# CPUBoard_p3.net
KiCad netlist of a schematic drawn in Altium Designer
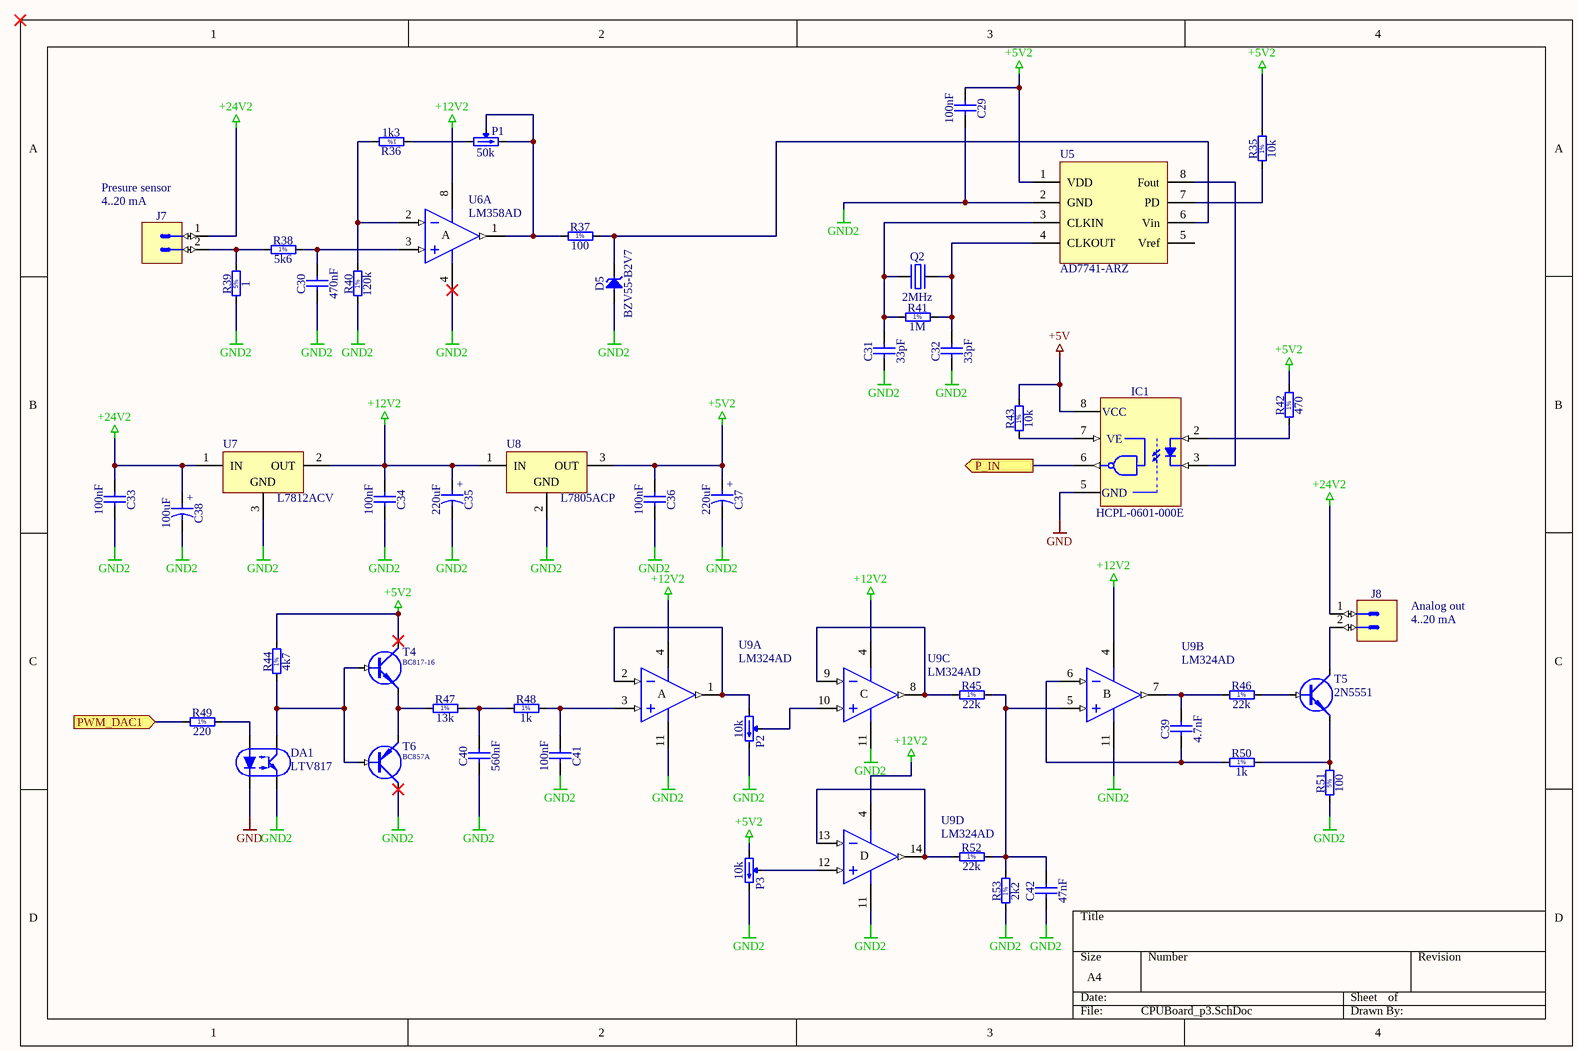
[diagram p0: CPUBoard_p3.SchDoc]

(export (version "E")
  (design (tool "Eeschema 10.0.6"))
  (components
    (comp (ref "C29")
      (value "100nF")
      (footprint "CAPC2012X135N")
      (description "Non-polarised capacitor")
      (fields
        (field (name "PART NUMBER") "CC0805_100NF_50V_10%_X7R")
        (field (name "VOLTAGE") "50V")
        (field (name "AUTHOR") "CERN DEM JLC")
      )
      (libsource (lib "Capacitors") (part "Capacitor - non polarized"))
    )
    (comp (ref "C30")
      (value "470nF")
      (footprint "CAPC2012X110N")
      (description "Non-polarised capacitor")
      (fields
        (field (name "PART NUMBER") "CC0805_470NF_50V_10%_X7R")
        (field (name "VOLTAGE") "50V")
        (field (name "AUTHOR") "CERN DEM JLC")
      )
      (libsource (lib "Capacitors") (part "Capacitor - non polarized"))
    )
    (comp (ref "C31")
      (value "33pF")
      (footprint "CAPC2012X135N")
      (description "Non-polarised capacitor")
      (fields
        (field (name "PART NUMBER") "CC0805_33PF_50V_5%_NP0")
        (field (name "VOLTAGE") "50V")
        (field (name "AUTHOR") "CERN DEM JLC")
      )
      (libsource (lib "Capacitors") (part "Capacitor - non polarized"))
    )
    (comp (ref "C32")
      (value "33pF")
      (footprint "CAPC2012X135N")
      (description "Non-polarised capacitor")
      (fields
        (field (name "PART NUMBER") "CC0805_33PF_50V_5%_NP0")
        (field (name "VOLTAGE") "50V")
        (field (name "AUTHOR") "CERN DEM JLC")
      )
      (libsource (lib "Capacitors") (part "Capacitor - non polarized"))
    )
    (comp (ref "C33")
      (value "100nF")
      (footprint "CAPC2012X135N")
      (description "Non-polarised capacitor")
      (fields
        (field (name "PART NUMBER") "CC0805_100NF_50V_10%_X7R")
        (field (name "VOLTAGE") "50V")
        (field (name "AUTHOR") "CERN DEM JLC")
      )
      (libsource (lib "Capacitors") (part "Capacitor - non polarized"))
    )
    (comp (ref "C34")
      (value "100nF")
      (footprint "CAPC2012X135N")
      (description "Non-polarised capacitor")
      (fields
        (field (name "PART NUMBER") "CC0805_100NF_50V_10%_X7R")
        (field (name "VOLTAGE") "50V")
        (field (name "AUTHOR") "CERN DEM JLC")
      )
      (libsource (lib "Capacitors") (part "Capacitor - non polarized"))
    )
    (comp (ref "C35")
      (value "220uF")
      (footprint "CAPPR350-850X1300")
      (description "Polarised capacitor")
      (fields
        (field (name "PART NUMBER") "CAER_220UF_25V_20%_RUBYCON_25YXF220M8X11.5")
        (field (name "VOLTAGE") "25V")
        (field (name "AUTHOR") "CERN DEM JLC")
      )
      (libsource (lib "Capacitors") (part "Capacitor - polarized"))
    )
    (comp (ref "C36")
      (value "100nF")
      (footprint "CAPC2012X135N")
      (description "Non-polarised capacitor")
      (fields
        (field (name "PART NUMBER") "CC0805_100NF_50V_10%_X7R")
        (field (name "VOLTAGE") "50V")
        (field (name "AUTHOR") "CERN DEM JLC")
      )
      (libsource (lib "Capacitors") (part "Capacitor - non polarized"))
    )
    (comp (ref "C37")
      (value "220uF")
      (footprint "CAPPR350-850X1300")
      (description "Polarised capacitor")
      (fields
        (field (name "PART NUMBER") "CAER_220UF_25V_20%_RUBYCON_25YXF220M8X11.5")
        (field (name "VOLTAGE") "25V")
        (field (name "AUTHOR") "CERN DEM JLC")
      )
      (libsource (lib "Capacitors") (part "Capacitor - polarized"))
    )
    (comp (ref "C38")
      (value "100uF")
      (footprint "CAPPR500-1050X1750")
      (description "Polarised capacitor")
      (fields
        (field (name "PART NUMBER") "CAER_100UF_63V_20%_500-1050X1750_LESR0R190")
        (field (name "VOLTAGE") "63V")
        (field (name "AUTHOR") "CERN DEM JLC")
      )
      (libsource (lib "Capacitors") (part "Capacitor - polarized"))
    )
    (comp (ref "C39")
      (value "4.7nF")
      (footprint "CAPC2012X135N")
      (description "Non-polarised capacitor")
      (fields
        (field (name "PART NUMBER") "CC0805_4.7NF_50V_10%_X7R")
        (field (name "VOLTAGE") "50V")
        (field (name "AUTHOR") "CERN DEM JLC")
      )
      (libsource (lib "Capacitors") (part "Capacitor - non polarized"))
    )
    (comp (ref "C40")
      (value "560nF")
      (footprint "CAPC2012X110N")
      (description "Non-polarised capacitor")
      (fields
        (field (name "PART NUMBER") "CC0805_470NF_50V_10%_X7R")
        (field (name "VOLTAGE") "50V")
        (field (name "AUTHOR") "CERN DEM JLC")
      )
      (libsource (lib "Capacitors") (part "Capacitor - non polarized"))
    )
    (comp (ref "C41")
      (value "100nF")
      (footprint "CAPC2012X135N")
      (description "Non-polarised capacitor")
      (fields
        (field (name "PART NUMBER") "CC0805_100NF_50V_10%_X7R")
        (field (name "VOLTAGE") "50V")
        (field (name "AUTHOR") "CERN DEM JLC")
      )
      (libsource (lib "Capacitors") (part "Capacitor - non polarized"))
    )
    (comp (ref "C42")
      (value "47nF")
      (footprint "CAPC2013X100N")
      (description "Non-polarised capacitor")
      (fields
        (field (name "PART NUMBER") "CC0805_47NF_50V_10%_X7R")
        (field (name "VOLTAGE") "50V")
        (field (name "AUTHOR") "CERN DEM JLC")
      )
      (libsource (lib "Capacitors") (part "Capacitor - non polarized"))
    )
    (comp (ref "D5")
      (value "BZV55-B2V7")
      (footprint "DIOMELF3515N")
      (description "Zener Diode")
      (fields
        (field (name "VOLTAGE") "2V7")
        (field (name "POWER") "500mW")
        (field (name "AUTHOR") "CERN DEM JLC")
      )
      (libsource (lib "ICs And Semiconductors") (part "Diode Zener"))
    )
    (comp (ref "DA1")
      (value "LTV817")
      (footprint "DIL4-300a")
      (libsource (lib "Opto Coupler") (part "LTV817"))
    )
    (comp (ref "IC1")
      (value "HCPL-0601-000E")
      (footprint "SOIC127P600X330-8N")
      (description "Single Optocoupler")
      (fields (field (name "MANUFACTURER") "AVAGO TECHNOLOGIES") (field (name "AUTHOR") "CERN DEM JLC"))
      (libsource (lib "ICs And Semiconductors") (part "Optocoupler Type8"))
    )
    (comp (ref "J7")
      (value "KK®")
      (footprint "MOLEX_22-27-2021")
      (description "Connector 2 Male")
      (fields
        (field (name "PART NUMBER") "MOLEX_22-27-2021")
        (field (name "MANUFACTURER") "MOLEX")
        (field (name "AUTHOR") "CERN DEM JLC")
      )
      (libsource (lib "Connectors") (part "Connector 2 Male"))
    )
    (comp (ref "J8")
      (value "KK®")
      (footprint "MOLEX_22-27-2021")
      (description "Connector 2 Male")
      (fields
        (field (name "PART NUMBER") "MOLEX_22-27-2021")
        (field (name "MANUFACTURER") "MOLEX")
        (field (name "AUTHOR") "CERN DEM JLC")
      )
      (libsource (lib "") (part "Connector 2 Male_1"))
    )
    (comp (ref "P1")
      (value "50k")
      (footprint "TRIM_BOURNS_3296Y")
      (description "Trimming Potentiometer")
      (fields
        (field (name "PART NUMBER") "TRIM_25T_50K_BOURNS_3296Y-1-503LF")
        (field (name "POWER") "0.5W")
        (field (name "AUTHOR") "CERN DEM JLC")
      )
      (libsource (lib "Resistors") (part "Trimming Potentiometer"))
    )
    (comp (ref "P2")
      (value "10k")
      (footprint "TRIM_BOURNS_3296Y")
      (description "Trimming Potentiometer")
      (fields
        (field (name "PART NUMBER") "TRIM_25T_10K_BOURNS_3296Y-1-103LF")
        (field (name "POWER") "0.5W")
        (field (name "AUTHOR") "CERN DEM JLC")
      )
      (libsource (lib "Resistors") (part "Trimming Potentiometer"))
    )
    (comp (ref "P3")
      (value "10k")
      (footprint "TRIM_BOURNS_3296Y")
      (description "Trimming Potentiometer")
      (fields
        (field (name "PART NUMBER") "TRIM_25T_10K_BOURNS_3296Y-1-103LF")
        (field (name "POWER") "0.5W")
        (field (name "AUTHOR") "CERN DEM JLC")
      )
      (libsource (lib "Resistors") (part "Trimming Potentiometer"))
    )
    (comp (ref "Q2")
      (value "2MHz")
      (footprint "XTAL_HC-49/U-S")
      (description "Quartz Crystal")
      (fields
        (field (name "PART NUMBER") "XTAL_5MHZ_CITIZEN_HC49US5.000MABJ-UB")
        (field (name "MANUFACTURER") "CITIZEN FINETECH MIYOTA CO")
        (field (name "AUTHOR") "CERN DEM JLC")
      )
      (libsource (lib "ICs And Semiconductors") (part "Quartz Crystal"))
    )
    (comp (ref "R35")
      (value "10k")
      (footprint "RESC2012X60N")
      (description "Resistor - 1%")
      (fields
        (field (name "PART NUMBER") "R0805_10K_1%_0.125W_100PPM")
        (field (name "POWER") "0.125W")
        (field (name "AUTHOR") "CERN DEM JLC")
      )
      (libsource (lib "Resistors") (part "Resistor - 1%"))
    )
    (comp (ref "R36")
      (value "1k3")
      (footprint "RESC2012X60N")
      (description "Resistor - 1%")
      (fields
        (field (name "PART NUMBER") "R0805_1K3_1%_0.125W_100PPM")
        (field (name "POWER") "0.125W")
        (field (name "AUTHOR") "CERN DEM JLC")
      )
      (libsource (lib "Resistors") (part "Resistor - 1%"))
    )
    (comp (ref "R37")
      (value "100")
      (footprint "RESC2012X60N")
      (description "Resistor - 1%")
      (fields
        (field (name "PART NUMBER") "R0805_100R_1%_0.125W_100PPM")
        (field (name "POWER") "0.125W")
        (field (name "AUTHOR") "CERN DEM JLC")
      )
      (libsource (lib "Resistors") (part "Resistor - 1%"))
    )
    (comp (ref "R38")
      (value "5k6")
      (footprint "RESC2012X60N")
      (description "Resistor - 1%")
      (fields
        (field (name "PART NUMBER") "R0805_5K6_1%_0.125W_100PPM")
        (field (name "POWER") "0.125W")
        (field (name "AUTHOR") "CERN DEM JLC")
      )
      (libsource (lib "Resistors") (part "Resistor - 1%"))
    )
    (comp (ref "R39")
      (value "1")
      (footprint "RESC3225X70N")
      (description "Resistor - 0,1%")
      (fields
        (field (name "PART NUMBER") "R1210_51R_5%_0.5W_200PPM_PANASONIC_ERJP")
        (field (name "POWER") "0.5W")
        (field (name "AUTHOR") "CERN DEM JLC")
      )
      (libsource (lib "Resistors") (part "Resistor - 5%"))
    )
    (comp (ref "R40")
      (value "120k")
      (footprint "RESC2012X60N")
      (description "Resistor - 1%")
      (fields
        (field (name "PART NUMBER") "R0805_120K_1%_0.125W_100PPM")
        (field (name "POWER") "0.125W")
        (field (name "AUTHOR") "CERN DEM JLC")
      )
      (libsource (lib "Resistors") (part "Resistor - 1%"))
    )
    (comp (ref "R41")
      (value "1M")
      (footprint "RESC2012X60N")
      (description "Resistor - 1%")
      (fields
        (field (name "PART NUMBER") "R0805_1M_1%_0.125W_100PPM")
        (field (name "POWER") "0.125W")
        (field (name "AUTHOR") "CERN DEM JLC")
      )
      (libsource (lib "Resistors") (part "Resistor - 1%"))
    )
    (comp (ref "R42")
      (value "470")
      (footprint "RESC2012X60N")
      (description "Resistor - 1%")
      (fields
        (field (name "PART NUMBER") "R0805_470R_1%_0.125W_100PPM")
        (field (name "POWER") "0.125W")
        (field (name "AUTHOR") "CERN DEM JLC")
      )
      (libsource (lib "Resistors") (part "Resistor - 1%"))
    )
    (comp (ref "R43")
      (value "10k")
      (footprint "RESC2012X60N")
      (description "Resistor - 1%")
      (fields
        (field (name "PART NUMBER") "R0805_10K_1%_0.125W_100PPM")
        (field (name "POWER") "0.125W")
        (field (name "AUTHOR") "CERN DEM JLC")
      )
      (libsource (lib "Resistors") (part "Resistor - 1%"))
    )
    (comp (ref "R44")
      (value "4k7")
      (footprint "RESC2012X60N")
      (description "Resistor - 1%")
      (fields
        (field (name "PART NUMBER") "R0805_4K7_1%_0.125W_100PPM")
        (field (name "POWER") "0.125W")
        (field (name "AUTHOR") "CERN DEM JLC")
      )
      (libsource (lib "Resistors") (part "Resistor - 1%"))
    )
    (comp (ref "R45")
      (value "22k")
      (footprint "RESC2012X60N")
      (description "Resistor - 1%")
      (fields
        (field (name "PART NUMBER") "R0805_22K_1%_0.125W_100PPM")
        (field (name "POWER") "0.125W")
        (field (name "AUTHOR") "CERN DEM JLC")
      )
      (libsource (lib "Resistors") (part "Resistor - 1%"))
    )
    (comp (ref "R46")
      (value "22k")
      (footprint "RESC2012X60N")
      (description "Resistor - 1%")
      (fields
        (field (name "PART NUMBER") "R0805_22K_1%_0.125W_100PPM")
        (field (name "POWER") "0.125W")
        (field (name "AUTHOR") "CERN DEM JLC")
      )
      (libsource (lib "Resistors") (part "Resistor - 1%"))
    )
    (comp (ref "R47")
      (value "13k")
      (footprint "RESC2012X60N")
      (description "Resistor - 1%")
      (fields
        (field (name "PART NUMBER") "R0805_13K_1%_0.125W_100PPM")
        (field (name "POWER") "0.125W")
        (field (name "AUTHOR") "CERN DEM JLC")
      )
      (libsource (lib "Resistors") (part "Resistor - 1%"))
    )
    (comp (ref "R48")
      (value "1k")
      (footprint "RESC2012X60N")
      (description "Resistor - 1%")
      (fields
        (field (name "PART NUMBER") "R0805_1K_1%_0.125W_100PPM")
        (field (name "POWER") "0.125W")
        (field (name "AUTHOR") "CERN DEM JLC")
      )
      (libsource (lib "Resistors") (part "Resistor - 1%"))
    )
    (comp (ref "R49")
      (value "220")
      (footprint "RESC2012X60N")
      (description "Resistor - 1%")
      (fields
        (field (name "PART NUMBER") "R0805_220R_1%_0.125W_100PPM")
        (field (name "POWER") "0.125W")
        (field (name "AUTHOR") "CERN DEM JLC")
      )
      (libsource (lib "Resistors") (part "Resistor - 1%"))
    )
    (comp (ref "R50")
      (value "1k")
      (footprint "RESC2012X60N")
      (description "Resistor - 1%")
      (fields
        (field (name "PART NUMBER") "R0805_1K_1%_0.125W_100PPM")
        (field (name "POWER") "0.125W")
        (field (name "AUTHOR") "CERN DEM JLC")
      )
      (libsource (lib "Resistors") (part "Resistor - 1%"))
    )
    (comp (ref "R51")
      (value "100")
      (footprint "RESC3225X70N")
      (description "Resistor - 0.1%")
      (fields
        (field (name "PART NUMBER") "R1210_100R_5%_0.5W_200PPM_PANASONIC_ERJP")
        (field (name "POWER") "0.5W")
        (field (name "AUTHOR") "CERN DEM JLC")
      )
      (libsource (lib "Resistors") (part "Resistor - 5%"))
    )
    (comp (ref "R52")
      (value "22k")
      (footprint "RESC2012X60N")
      (description "Resistor - 1%")
      (fields
        (field (name "PART NUMBER") "R0805_22K_1%_0.125W_100PPM")
        (field (name "POWER") "0.125W")
        (field (name "AUTHOR") "CERN DEM JLC")
      )
      (libsource (lib "Resistors") (part "Resistor - 1%"))
    )
    (comp (ref "R53")
      (value "2k2")
      (footprint "RESC2012X60N")
      (description "Resistor - 1%")
      (fields
        (field (name "PART NUMBER") "R0805_2K2_1%_0.125W_100PPM")
        (field (name "POWER") "0.125W")
        (field (name "AUTHOR") "CERN DEM JLC")
      )
      (libsource (lib "Resistors") (part "Resistor - 1%"))
    )
    (comp (ref "T4")
      (value "BC817-16")
      (footprint "SOT23")
      (description "SMD-SOT23")
      (libsource (lib "BJT") (part "BC817-16"))
    )
    (comp (ref "T5")
      (value "2N5551")
      (footprint "TO92C1")
      (description "150V 0.5A 100MHz 6p (10V)")
      (libsource (lib "BJT") (part "2N5551"))
    )
    (comp (ref "T6")
      (value "BC857A")
      (footprint "SOT23")
      (description "SMD-SOT23")
      (libsource (lib "BJT") (part "BC857A"))
    )
    (comp (ref "U5")
      (value "AD7741-ARZ")
      (footprint "SOIC8 8S1_M")
      (libsource (lib "PowerLib") (part "AD7741-ARZ"))
    )
    (comp (ref "U6")
      (value "LM358AD")
      (footprint "SO8_N")
      (description "Low-Power Dual Operational Amplifier")
      (fields (field (name "PUBLISHER") "Altium Limited"))
      (libsource (lib "ST Operational Amplifier") (part "LM358AD"))
    )
    (comp (ref "U7")
      (value "L7812ACV")
      (footprint "TO220ABN")
      (description "Precision 1A Regulator")
      (fields (field (name "PUBLISHER") "Altium Limited"))
      (libsource (lib "ST Power Mgt Voltage Regulator") (part "L7812ACV"))
    )
    (comp (ref "U8")
      (value "L7805ACP")
      (footprint "TO220FP")
      (description "Positive Voltage Regulator, 5V, 3-Pin TO-220FP")
      (libsource (lib "STMicroelectronics Power Management Linear Regulator") (part "L7805ACP"))
    )
    (comp (ref "U9")
      (value "LM324AD")
      (footprint "SO14_N")
      (description "Low-Power Quad Operational Amplifier")
      (fields (field (name "PUBLISHER") "Altium Limited"))
      (libsource (lib "ST Operational Amplifier") (part "LM324AD"))
    )
  )
  (nets
    (net (code "1") (name "+5V") (class "Default")
      (node (ref "IC1") (pin "8") (pinfunction "VCC_8") (pintype "power_in"))
      (node (ref "R43") (pin "2") (pinfunction "2_2") (pintype "passive"))
    )
    (net (code "2") (name "+5V2") (class "Default")
      (node (ref "C29") (pin "1") (pinfunction "1_1") (pintype "passive"))
      (node (ref "C36") (pin "1") (pinfunction "1_1") (pintype "passive"))
      (node (ref "C37") (pin "1") (pinfunction "1_1") (pintype "passive"))
      (node (ref "P3") (pin "1") (pinfunction "CCW_1") (pintype "passive"))
      (node (ref "R35") (pin "2") (pinfunction "2_2") (pintype "passive"))
      (node (ref "R42") (pin "2") (pinfunction "2_2") (pintype "passive"))
      (node (ref "R44") (pin "2") (pinfunction "2_2") (pintype "passive"))
      (node (ref "T4") (pin "3") (pinfunction "C_3") (pintype "open_collector"))
      (node (ref "U5") (pin "1") (pinfunction "VDD_1") (pintype "passive"))
      (node (ref "U8") (pin "3") (pinfunction "OUT_3") (pintype "power_in"))
    )
    (net (code "3") (name "+12V2") (class "Default")
      (node (ref "C34") (pin "1") (pinfunction "1_1") (pintype "passive"))
      (node (ref "C35") (pin "1") (pinfunction "1_1") (pintype "passive"))
      (node (ref "U6") (pin "8") (pinfunction "V+_8") (pintype "power_in"))
      (node (ref "U7") (pin "2") (pinfunction "OUT_2") (pintype "power_in"))
      (node (ref "U8") (pin "1") (pinfunction "IN_1") (pintype "power_in"))
      (node (ref "U9") (pin "4") (pinfunction "V+_4") (pintype "power_in"))
    )
    (net (code "4") (name "+24V2") (class "Default")
      (node (ref "C33") (pin "1") (pinfunction "1_1") (pintype "passive"))
      (node (ref "C38") (pin "1") (pinfunction "1_1") (pintype "passive"))
      (node (ref "J7") (pin "1") (pinfunction "1_1") (pintype "bidirectional"))
      (node (ref "J8") (pin "1") (pinfunction "1_1") (pintype "bidirectional"))
      (node (ref "U7") (pin "1") (pinfunction "IN_1") (pintype "power_in"))
    )
    (net (code "5") (name "/PWM_DAC1") (class "Default")
      (node (ref "R49") (pin "1") (pinfunction "1_1") (pintype "passive"))
    )
    (net (code "6") (name "/P_IN") (class "Default")
      (node (ref "IC1") (pin "6") (pinfunction "VO_6") (pintype "output"))
    )
    (net (code "7") (name "GND") (class "Default")
      (node (ref "DA1") (pin "2") (pinfunction "C_2") (pintype "passive"))
      (node (ref "IC1") (pin "5") (pinfunction "GND_5") (pintype "power_in"))
    )
    (net (code "8") (name "GND2") (class "Default")
      (node (ref "C29") (pin "2") (pinfunction "2_2") (pintype "passive"))
      (node (ref "C30") (pin "1") (pinfunction "1_1") (pintype "passive"))
      (node (ref "C31") (pin "1") (pinfunction "1_1") (pintype "passive"))
      (node (ref "C32") (pin "1") (pinfunction "1_1") (pintype "passive"))
      (node (ref "C33") (pin "2") (pinfunction "2_2") (pintype "passive"))
      (node (ref "C34") (pin "2") (pinfunction "2_2") (pintype "passive"))
      (node (ref "C35") (pin "2") (pinfunction "2_2") (pintype "passive"))
      (node (ref "C36") (pin "2") (pinfunction "2_2") (pintype "passive"))
      (node (ref "C37") (pin "2") (pinfunction "2_2") (pintype "passive"))
      (node (ref "C38") (pin "2") (pinfunction "2_2") (pintype "passive"))
      (node (ref "C40") (pin "1") (pinfunction "1_1") (pintype "passive"))
      (node (ref "C41") (pin "2") (pinfunction "2_2") (pintype "passive"))
      (node (ref "C42") (pin "1") (pinfunction "1_1") (pintype "passive"))
      (node (ref "D5") (pin "2") (pinfunction "A_2") (pintype "passive"))
      (node (ref "DA1") (pin "3") (pinfunction "E_3") (pintype "passive"))
      (node (ref "P2") (pin "3") (pinfunction "CW_3") (pintype "passive"))
      (node (ref "P3") (pin "3") (pinfunction "CW_3") (pintype "passive"))
      (node (ref "R39") (pin "1") (pinfunction "1_1") (pintype "passive"))
      (node (ref "R40") (pin "1") (pinfunction "1_1") (pintype "passive"))
      (node (ref "R51") (pin "1") (pinfunction "1_1") (pintype "passive"))
      (node (ref "R53") (pin "1") (pinfunction "1_1") (pintype "passive"))
      (node (ref "T6") (pin "3") (pinfunction "C_3") (pintype "open_collector"))
      (node (ref "U5") (pin "2") (pinfunction "GND_2") (pintype "passive"))
      (node (ref "U6") (pin "4") (pinfunction "V-_4") (pintype "power_in"))
      (node (ref "U7") (pin "3") (pinfunction "GND_3") (pintype "power_in"))
      (node (ref "U8") (pin "2") (pinfunction "GND_2") (pintype "power_in"))
      (node (ref "U9") (pin "11") (pinfunction "V-_11") (pintype "power_in"))
    )
    (net (code "9") (name "Net-(C40-Pad2)") (class "Default")
      (node (ref "C40") (pin "2") (pinfunction "2_2") (pintype "passive"))
      (node (ref "R47") (pin "2") (pinfunction "2_2") (pintype "passive"))
      (node (ref "R48") (pin "1") (pinfunction "1_1") (pintype "passive"))
    )
    (net (code "10") (name "Net-(D5-C)") (class "Default")
      (node (ref "D5") (pin "1") (pinfunction "C_1") (pintype "passive"))
      (node (ref "R37") (pin "2") (pinfunction "2_2") (pintype "passive"))
      (node (ref "U5") (pin "6") (pinfunction "Vin_6") (pintype "passive"))
    )
    (net (code "11") (name "Net-(DA1-A)") (class "Default")
      (node (ref "DA1") (pin "1") (pinfunction "A_1") (pintype "passive"))
      (node (ref "R49") (pin "2") (pinfunction "2_2") (pintype "passive"))
    )
    (net (code "12") (name "Net-(IC1-A)") (class "Default")
      (node (ref "IC1") (pin "2") (pinfunction "A_2") (pintype "input"))
      (node (ref "R42") (pin "1") (pinfunction "1_1") (pintype "passive"))
    )
    (net (code "13") (name "Net-(IC1-K)") (class "Default")
      (node (ref "IC1") (pin "3") (pinfunction "K_3") (pintype "input"))
      (node (ref "U5") (pin "8") (pinfunction "Fout_8") (pintype "passive"))
    )
    (net (code "14") (name "Net-(IC1-VE)") (class "Default")
      (node (ref "IC1") (pin "7") (pinfunction "VE_7") (pintype "input"))
      (node (ref "R43") (pin "1") (pinfunction "1_1") (pintype "passive"))
    )
    (net (code "15") (name "Net-(J7-Pad2)") (class "Default")
      (node (ref "J7") (pin "2") (pinfunction "2_2") (pintype "bidirectional"))
      (node (ref "R38") (pin "1") (pinfunction "1_1") (pintype "passive"))
      (node (ref "R39") (pin "2") (pinfunction "2_2") (pintype "passive"))
    )
    (net (code "16") (name "Net-(P1-CCW)") (class "Default")
      (node (ref "P1") (pin "1") (pinfunction "CCW_1") (pintype "passive"))
      (node (ref "R36") (pin "1") (pinfunction "1_1") (pintype "passive"))
    )
    (net (code "17") (name "Net-(P1-CW)") (class "Default")
      (node (ref "P1") (pin "2") (pinfunction "W_2") (pintype "passive"))
      (node (ref "P1") (pin "3") (pinfunction "CW_3") (pintype "passive"))
      (node (ref "R37") (pin "1") (pinfunction "1_1") (pintype "passive"))
      (node (ref "U6") (pin "1") (pinfunction "OUT_1") (pintype "output"))
    )
    (net (code "18") (name "Net-(P2-CCW)") (class "Default")
      (node (ref "P2") (pin "1") (pinfunction "CCW_1") (pintype "passive"))
      (node (ref "U9") (pin "1") (pinfunction "OUT_1") (pintype "output"))
      (node (ref "U9") (pin "2") (pinfunction "IN-_2") (pintype "input"))
    )
    (net (code "19") (name "Net-(P2-W)") (class "Default")
      (node (ref "P2") (pin "2") (pinfunction "W_2") (pintype "passive"))
      (node (ref "U9") (pin "10") (pinfunction "IN+_10") (pintype "input"))
    )
    (net (code "20") (name "Net-(P3-W)") (class "Default")
      (node (ref "P3") (pin "2") (pinfunction "W_2") (pintype "passive"))
      (node (ref "U9") (pin "12") (pinfunction "IN+_12") (pintype "input"))
    )
    (net (code "21") (name "Net-(Q2-OSC1)") (class "Default")
      (node (ref "C31") (pin "2") (pinfunction "2_2") (pintype "passive"))
      (node (ref "Q2") (pin "1") (pinfunction "OSC1_1") (pintype "passive"))
      (node (ref "R41") (pin "1") (pinfunction "1_1") (pintype "passive"))
      (node (ref "U5") (pin "3") (pinfunction "CLKIN_3") (pintype "passive"))
    )
    (net (code "22") (name "Net-(Q2-OSC2)") (class "Default")
      (node (ref "C32") (pin "2") (pinfunction "2_2") (pintype "passive"))
      (node (ref "Q2") (pin "2") (pinfunction "OSC2_2") (pintype "passive"))
      (node (ref "R41") (pin "2") (pinfunction "2_2") (pintype "passive"))
      (node (ref "U5") (pin "4") (pinfunction "CLKOUT_4") (pintype "passive"))
    )
    (net (code "23") (name "Net-(T4-B)") (class "Default")
      (node (ref "DA1") (pin "4") (pinfunction "C_4") (pintype "passive"))
      (node (ref "R44") (pin "1") (pinfunction "1_1") (pintype "passive"))
      (node (ref "T4") (pin "1") (pinfunction "B_1") (pintype "input"))
      (node (ref "T6") (pin "1") (pinfunction "B_1") (pintype "input"))
    )
    (net (code "24") (name "Net-(T4-E)") (class "Default")
      (node (ref "R47") (pin "1") (pinfunction "1_1") (pintype "passive"))
      (node (ref "T4") (pin "2") (pinfunction "E_2") (pintype "open_emitter"))
      (node (ref "T6") (pin "2") (pinfunction "E_2") (pintype "open_emitter"))
    )
    (net (code "25") (name "Net-(T5-B)") (class "Default")
      (node (ref "R46") (pin "2") (pinfunction "2_2") (pintype "passive"))
      (node (ref "T5") (pin "2") (pinfunction "B_2") (pintype "input"))
    )
    (net (code "26") (name "Net-(T5-C)") (class "Default")
      (node (ref "J8") (pin "2") (pinfunction "2_2") (pintype "bidirectional"))
      (node (ref "T5") (pin "1") (pinfunction "C_1") (pintype "open_collector"))
    )
    (net (code "27") (name "Net-(T5-E)") (class "Default")
      (node (ref "R50") (pin "2") (pinfunction "2_2") (pintype "passive"))
      (node (ref "R51") (pin "2") (pinfunction "2_2") (pintype "passive"))
      (node (ref "T5") (pin "3") (pinfunction "E_3") (pintype "open_emitter"))
    )
    (net (code "28") (name "Net-(U5-PD)") (class "Default")
      (node (ref "R35") (pin "1") (pinfunction "1_1") (pintype "passive"))
      (node (ref "U5") (pin "7") (pinfunction "PD_7") (pintype "passive"))
    )
    (net (code "29") (name "Net-(U6A-IN+)") (class "Default")
      (node (ref "C30") (pin "2") (pinfunction "2_2") (pintype "passive"))
      (node (ref "R38") (pin "2") (pinfunction "2_2") (pintype "passive"))
      (node (ref "U6") (pin "3") (pinfunction "IN+_3") (pintype "input"))
    )
    (net (code "30") (name "Net-(U6A-IN-)") (class "Default")
      (node (ref "R36") (pin "2") (pinfunction "2_2") (pintype "passive"))
      (node (ref "R40") (pin "2") (pinfunction "2_2") (pintype "passive"))
      (node (ref "U6") (pin "2") (pinfunction "IN-_2") (pintype "input"))
    )
    (net (code "31") (name "Net-(U9A-IN+)") (class "Default")
      (node (ref "C41") (pin "1") (pinfunction "1_1") (pintype "passive"))
      (node (ref "R48") (pin "2") (pinfunction "2_2") (pintype "passive"))
      (node (ref "U9") (pin "3") (pinfunction "IN+_3") (pintype "input"))
    )
    (net (code "32") (name "Net-(U9B-IN+)") (class "Default")
      (node (ref "C42") (pin "2") (pinfunction "2_2") (pintype "passive"))
      (node (ref "R45") (pin "2") (pinfunction "2_2") (pintype "passive"))
      (node (ref "R52") (pin "2") (pinfunction "2_2") (pintype "passive"))
      (node (ref "R53") (pin "2") (pinfunction "2_2") (pintype "passive"))
      (node (ref "U9") (pin "5") (pinfunction "IN+_5") (pintype "input"))
    )
    (net (code "33") (name "Net-(U9B-IN-)") (class "Default")
      (node (ref "C39") (pin "1") (pinfunction "1_1") (pintype "passive"))
      (node (ref "R50") (pin "1") (pinfunction "1_1") (pintype "passive"))
      (node (ref "U9") (pin "6") (pinfunction "IN-_6") (pintype "input"))
    )
    (net (code "34") (name "Net-(U9B-OUT)") (class "Default")
      (node (ref "C39") (pin "2") (pinfunction "2_2") (pintype "passive"))
      (node (ref "R46") (pin "1") (pinfunction "1_1") (pintype "passive"))
      (node (ref "U9") (pin "7") (pinfunction "OUT_7") (pintype "output"))
    )
    (net (code "35") (name "Net-(U9C-IN-)") (class "Default")
      (node (ref "R45") (pin "1") (pinfunction "1_1") (pintype "passive"))
      (node (ref "U9") (pin "8") (pinfunction "OUT_8") (pintype "output"))
      (node (ref "U9") (pin "9") (pinfunction "IN-_9") (pintype "input"))
    )
    (net (code "36") (name "Net-(U9D-IN-)") (class "Default")
      (node (ref "R52") (pin "1") (pinfunction "1_1") (pintype "passive"))
      (node (ref "U9") (pin "13") (pinfunction "IN-_13") (pintype "input"))
      (node (ref "U9") (pin "14") (pinfunction "OUT_14") (pintype "output"))
    )
    (net (code "37") (name "unconnected-(U5-Vref-Pad5)") (class "Default")
      (node (ref "U5") (pin "5") (pinfunction "Vref_5") (pintype "passive"))
    )
  )
)
